# FW9WR46HUY4A811.net
KiCad netlist of a schematic drawn in EAGLE
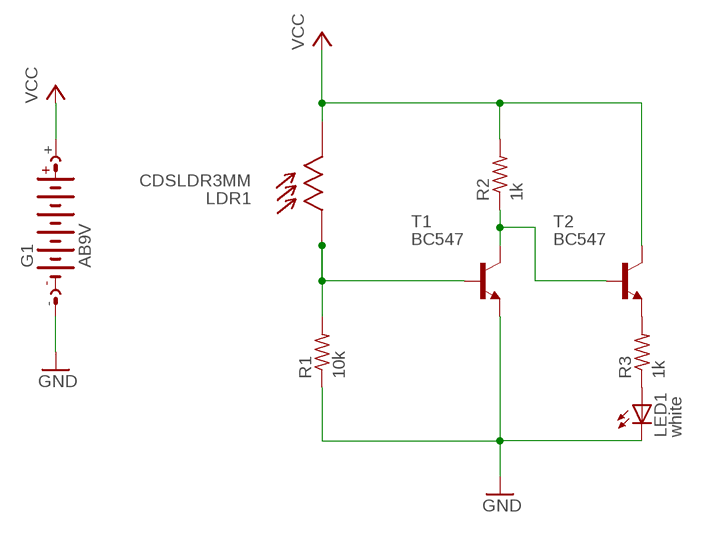
[diagram p0: schematic, sheet 1]

(export (version "E")
  (design (tool "Eeschema 10.0.6"))
  (components
    (comp (ref "G1")
      (value "AB9V")
      (footprint "eagle-import:AB9V")
      (libsource (lib "eagle-import") (part "AB9V"))
    )
    (comp (ref "LDR1")
      (value "CDSLDR3MM")
      (footprint "eagle-import:LDR3MM")
      (libsource (lib "eagle-import") (part "CDSLDR3MM"))
    )
    (comp (ref "LED1")
      (value "white")
      (footprint "eagle-import:LED5MM")
      (libsource (lib "eagle-import") (part "LED5MM"))
    )
    (comp (ref "R1")
      (value "10k")
      (footprint "eagle-import:0204_7")
      (libsource (lib "eagle-import") (part "R-US_0204/7"))
    )
    (comp (ref "R2")
      (value "1k")
      (footprint "eagle-import:0204_7")
      (libsource (lib "eagle-import") (part "R-US_0204/7"))
    )
    (comp (ref "R3")
      (value "1k")
      (footprint "eagle-import:0204_7")
      (libsource (lib "eagle-import") (part "R-US_0204/7"))
    )
    (comp (ref "T1")
      (value "BC547")
      (footprint "eagle-import:TO92")
      (libsource (lib "eagle-import") (part "BC547"))
    )
    (comp (ref "T2")
      (value "BC547")
      (footprint "eagle-import:TO92")
      (libsource (lib "eagle-import") (part "BC547"))
    )
  )
  (nets
    (net (code "1") (name "GND") (class "Default")
      (node (ref "G1") (pin "-") (pinfunction "-_-") (pintype "passive"))
      (node (ref "LED1") (pin "K") (pinfunction "C_K") (pintype "passive"))
      (node (ref "R1") (pin "1") (pinfunction "1_1") (pintype "passive"))
      (node (ref "T1") (pin "1") (pinfunction "E_1") (pintype "passive"))
    )
    (net (code "2") (name "Net-(LED1-PadA)") (class "Default")
      (node (ref "LED1") (pin "A") (pinfunction "A_A") (pintype "passive"))
      (node (ref "R3") (pin "1") (pinfunction "1_1") (pintype "passive"))
    )
    (net (code "3") (name "Net-(T1-B)") (class "Default")
      (node (ref "LDR1") (pin "P$1") (pinfunction "P$1_P$1") (pintype "bidirectional"))
      (node (ref "R1") (pin "2") (pinfunction "2_2") (pintype "passive"))
      (node (ref "T1") (pin "2") (pinfunction "B_2") (pintype "passive"))
    )
    (net (code "4") (name "Net-(T1-C)") (class "Default")
      (node (ref "R2") (pin "1") (pinfunction "1_1") (pintype "passive"))
      (node (ref "T1") (pin "3") (pinfunction "C_3") (pintype "passive"))
      (node (ref "T2") (pin "2") (pinfunction "B_2") (pintype "passive"))
    )
    (net (code "5") (name "Net-(T2-E)") (class "Default")
      (node (ref "R3") (pin "2") (pinfunction "2_2") (pintype "passive"))
      (node (ref "T2") (pin "1") (pinfunction "E_1") (pintype "passive"))
    )
    (net (code "6") (name "VCC") (class "Default")
      (node (ref "G1") (pin "+") (pinfunction "+_+") (pintype "passive"))
      (node (ref "LDR1") (pin "P$2") (pinfunction "P$2_P$2") (pintype "bidirectional"))
      (node (ref "R2") (pin "2") (pinfunction "2_2") (pintype "passive"))
      (node (ref "T2") (pin "3") (pinfunction "C_3") (pintype "passive"))
    )
  )
)
